# Sheet1.net
KiCad netlist of a schematic drawn in Altium Designer
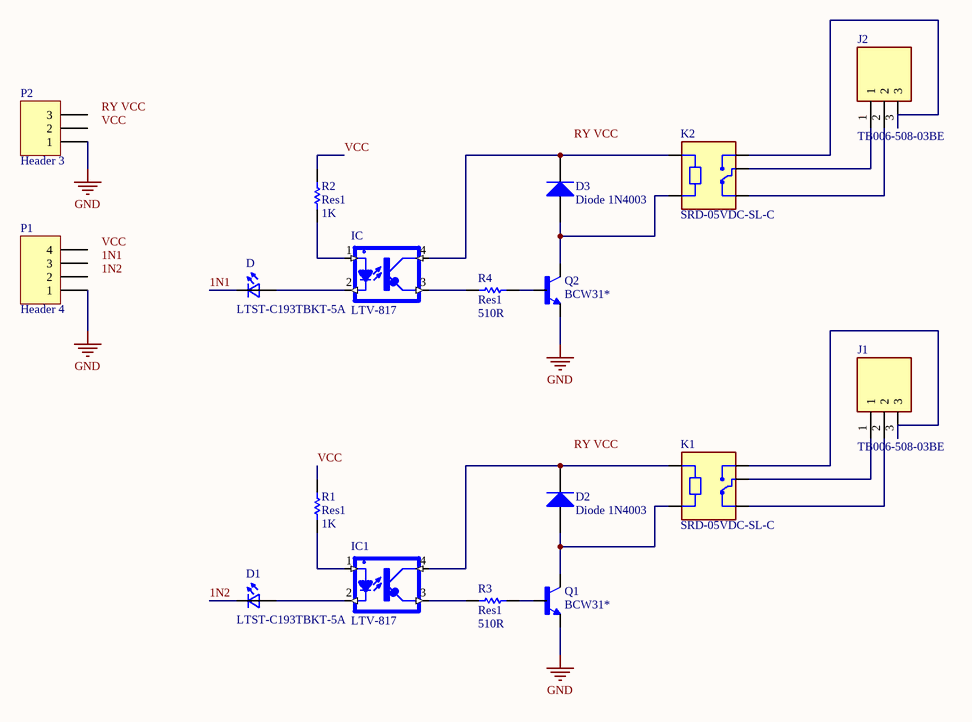
[diagram p0: Sheet1.SchDoc]

(export (version "E")
  (design (tool "Eeschema 10.0.6"))
  (components
    (comp (ref "D")
      (value "LTST-C193TBKT-5A")
      (footprint "0603")
      (description "Blue 470nm LED Indication - Discrete 2.8V 0603 _1608 Metric_")
      (fields (field (name "DIGI-KEY_PART_NUMBER") "160-1827-1-ND") (field (name "MF") "Lite-On Inc."))
      (libsource (lib "SnapEDAsch") (part "LTST-C193TBKT-5A"))
    )
    (comp (ref "D1")
      (value "LTST-C193TBKT-5A")
      (footprint "0603")
      (description "Blue 470nm LED Indication - Discrete 2.8V 0603 _1608 Metric_")
      (fields (field (name "DIGI-KEY_PART_NUMBER") "160-1827-1-ND") (field (name "MF") "Lite-On Inc."))
      (libsource (lib "SnapEDAsch") (part "LTST-C193TBKT-5A"))
    )
    (comp (ref "D2")
      (value "Diode 1N4003")
      (footprint "DO-41")
      (description "1 Amp General Purpose Rectifier")
      (fields (field (name "PUBLISHER") "Altium Limited"))
      (libsource (lib "Miscellaneous Devices") (part "Diode 1N4003"))
    )
    (comp (ref "D3")
      (value "Diode 1N4003")
      (footprint "DO-41")
      (description "1 Amp General Purpose Rectifier")
      (fields (field (name "PUBLISHER") "Altium Limited"))
      (libsource (lib "Miscellaneous Devices") (part "Diode 1N4003"))
    )
    (comp (ref "IC")
      (value "LTV-817")
      (footprint "DIP-4")
      (description "Optoisolator Transistor Output 5000Vrms 1 Channel 4-SMD")
      (fields (field (name "MF") "Lite-On Electronics"))
      (libsource (lib "SnapEDAsch") (part "LTV-817"))
    )
    (comp (ref "IC1")
      (value "LTV-817")
      (footprint "DIP-4")
      (description "Optoisolator Transistor Output 5000Vrms 1 Channel 4-SMD")
      (fields (field (name "MF") "Lite-On Electronics"))
      (libsource (lib "SnapEDAsch") (part "LTV-817"))
    )
    (comp (ref "J1")
      (value "TB006-508-03BE")
      (footprint "CUI_TB006-508-03BE")
      (description "2~24 Poles, Screw Type, Horizontal, 5.08 Pitch, 26~14 (AWG), Terminal Block Connector")
      (fields (field (name "MF") "CUI Devices"))
      (libsource (lib "TB006-508-03BE") (part "TB006-508-03BE"))
    )
    (comp (ref "J2")
      (value "TB006-508-03BE")
      (footprint "CUI_TB006-508-03BE")
      (description "2~24 Poles, Screw Type, Horizontal, 5.08 Pitch, 26~14 (AWG), Terminal Block Connector")
      (fields (field (name "MF") "CUI Devices"))
      (libsource (lib "TB006-508-03BE") (part "TB006-508-03BE"))
    )
    (comp (ref "K1")
      (value "SRD-05VDC-SL-C")
      (footprint "RELAY_SRD-05VDC-SL-C")
      (fields (field (name "MF") "Songle Relay"))
      (libsource (lib "SRD-05VDC-SL-C") (part "SRD-05VDC-SL-C"))
    )
    (comp (ref "K2")
      (value "SRD-05VDC-SL-C")
      (footprint "RELAY_SRD-05VDC-SL-C")
      (fields (field (name "MF") "Songle Relay"))
      (libsource (lib "SRD-05VDC-SL-C") (part "SRD-05VDC-SL-C"))
    )
    (comp (ref "P1")
      (value "Header 4")
      (footprint "HDR1X4")
      (description "Header, 4-Pin")
      (fields (field (name "PUBLISHER") "Altium Limited"))
      (libsource (lib "Miscellaneous Connectors") (part "Header 4"))
    )
    (comp (ref "P2")
      (value "Header 3")
      (footprint "HDR1X3")
      (description "Header, 3-Pin")
      (fields (field (name "PUBLISHER") "Altium Limited"))
      (libsource (lib "Miscellaneous Connectors") (part "Header 3"))
    )
    (comp (ref "Q1")
      (value "BCW31*")
      (footprint "SOT23-BEC")
      (description "Bipolar (BJT) Transistor NPN General Purpose Amplifier Surface Mount")
      (fields (field (name "MF") "ON Semiconductor") (field (name "MP") "BCW31"))
      (libsource (lib "BCW31") (part "BCW31*"))
    )
    (comp (ref "Q2")
      (value "BCW31*")
      (footprint "SOT23-BEC")
      (description "Bipolar (BJT) Transistor NPN General Purpose Amplifier Surface Mount")
      (fields (field (name "MF") "ON Semiconductor") (field (name "MP") "BCW31"))
      (libsource (lib "BCW31") (part "BCW31*"))
    )
    (comp (ref "R1")
      (value "Res1")
      (footprint "AXIAL-0.3")
      (description "Resistor")
      (fields (field (name "ALTIUM_VALUE") "1K") (field (name "PUBLISHER") "Altium Limited"))
      (libsource (lib "Miscellaneous Devices") (part "Res1"))
    )
    (comp (ref "R2")
      (value "Res1")
      (footprint "AXIAL-0.3")
      (description "Resistor")
      (fields (field (name "ALTIUM_VALUE") "1K") (field (name "PUBLISHER") "Altium Limited"))
      (libsource (lib "Miscellaneous Devices") (part "Res1"))
    )
    (comp (ref "R3")
      (value "Res1")
      (footprint "AXIAL-0.3")
      (description "Resistor")
      (fields (field (name "ALTIUM_VALUE") "510R") (field (name "PUBLISHER") "Altium Limited"))
      (libsource (lib "Miscellaneous Devices") (part "Res1"))
    )
    (comp (ref "R4")
      (value "Res1")
      (footprint "AXIAL-0.3")
      (description "Resistor")
      (fields (field (name "ALTIUM_VALUE") "510R") (field (name "PUBLISHER") "Altium Limited"))
      (libsource (lib "Miscellaneous Devices") (part "Res1"))
    )
  )
  (nets
    (net (code "1") (name "/1N1") (class "Default")
      (node (ref "D") (pin "1") (pinfunction "K2_1") (pintype "passive"))
    )
    (net (code "2") (name "/1N2") (class "Default")
      (node (ref "D1") (pin "1") (pinfunction "K2_1") (pintype "passive"))
    )
    (net (code "4") (name "/VCC") (class "Default")
      (node (ref "R1") (pin "2") (pinfunction "2_2") (pintype "passive"))
      (node (ref "R2") (pin "2") (pinfunction "2_2") (pintype "passive"))
    )
    (net (code "5") (name "GND") (class "Default")
      (node (ref "P1") (pin "1") (pinfunction "1_1") (pintype "passive"))
      (node (ref "P2") (pin "1") (pinfunction "1_1") (pintype "passive"))
      (node (ref "Q1") (pin "E") (pinfunction "E_E") (pintype "passive"))
      (node (ref "Q2") (pin "E") (pinfunction "E_E") (pintype "passive"))
    )
    (net (code "6") (name "Net-(D-A2)") (class "Default")
      (node (ref "D") (pin "2") (pinfunction "A2_2") (pintype "passive"))
      (node (ref "IC") (pin "2") (pinfunction "2_2") (pintype "output"))
    )
    (net (code "7") (name "Net-(D1-A2)") (class "Default")
      (node (ref "D1") (pin "2") (pinfunction "A2_2") (pintype "passive"))
      (node (ref "IC1") (pin "2") (pinfunction "2_2") (pintype "output"))
    )
    (net (code "8") (name "Net-(D2-A)") (class "Default")
      (node (ref "D2") (pin "1") (pinfunction "A_1") (pintype "passive"))
      (node (ref "K1") (pin "A2") (pinfunction "A2_A2") (pintype "passive"))
      (node (ref "Q1") (pin "C") (pinfunction "C_C") (pintype "passive"))
    )
    (net (code "9") (name "Net-(D2-K)") (class "Default")
      (node (ref "D2") (pin "2") (pinfunction "K_2") (pintype "passive"))
      (node (ref "IC1") (pin "4") (pinfunction "4_4") (pintype "input"))
      (node (ref "K1") (pin "A1") (pinfunction "A1_A1") (pintype "passive"))
    )
    (net (code "10") (name "Net-(D3-A)") (class "Default")
      (node (ref "D3") (pin "1") (pinfunction "A_1") (pintype "passive"))
      (node (ref "K2") (pin "A2") (pinfunction "A2_A2") (pintype "passive"))
      (node (ref "Q2") (pin "C") (pinfunction "C_C") (pintype "passive"))
    )
    (net (code "11") (name "Net-(D3-K)") (class "Default")
      (node (ref "D3") (pin "2") (pinfunction "K_2") (pintype "passive"))
      (node (ref "IC") (pin "4") (pinfunction "4_4") (pintype "input"))
      (node (ref "K2") (pin "A1") (pinfunction "A1_A1") (pintype "passive"))
    )
    (net (code "12") (name "Net-(IC-Pad1)") (class "Default")
      (node (ref "IC") (pin "1") (pinfunction "1_1") (pintype "input"))
      (node (ref "R2") (pin "1") (pinfunction "1_1") (pintype "passive"))
    )
    (net (code "13") (name "Net-(IC-Pad3)") (class "Default")
      (node (ref "IC") (pin "3") (pinfunction "3_3") (pintype "output"))
      (node (ref "R4") (pin "1") (pinfunction "1_1") (pintype "passive"))
    )
    (net (code "14") (name "Net-(IC1-Pad1)") (class "Default")
      (node (ref "IC1") (pin "1") (pinfunction "1_1") (pintype "input"))
      (node (ref "R1") (pin "1") (pinfunction "1_1") (pintype "passive"))
    )
    (net (code "15") (name "Net-(IC1-Pad3)") (class "Default")
      (node (ref "IC1") (pin "3") (pinfunction "3_3") (pintype "output"))
      (node (ref "R3") (pin "1") (pinfunction "1_1") (pintype "passive"))
    )
    (net (code "16") (name "Net-(J1-Pad1)") (class "Default")
      (node (ref "J1") (pin "1") (pinfunction "1_1") (pintype "passive"))
      (node (ref "K1") (pin "COM") (pinfunction "COM_COM") (pintype "passive"))
    )
    (net (code "17") (name "Net-(J1-Pad2)") (class "Default")
      (node (ref "J1") (pin "2") (pinfunction "2_2") (pintype "passive"))
      (node (ref "K1") (pin "NC") (pinfunction "NC_NC") (pintype "passive"))
    )
    (net (code "18") (name "Net-(J1-Pad3)") (class "Default")
      (node (ref "J1") (pin "3") (pinfunction "3_3") (pintype "passive"))
      (node (ref "K1") (pin "NO") (pinfunction "NO_NO") (pintype "passive"))
    )
    (net (code "19") (name "Net-(J2-Pad1)") (class "Default")
      (node (ref "J2") (pin "1") (pinfunction "1_1") (pintype "passive"))
      (node (ref "K2") (pin "COM") (pinfunction "COM_COM") (pintype "passive"))
    )
    (net (code "20") (name "Net-(J2-Pad2)") (class "Default")
      (node (ref "J2") (pin "2") (pinfunction "2_2") (pintype "passive"))
      (node (ref "K2") (pin "NC") (pinfunction "NC_NC") (pintype "passive"))
    )
    (net (code "21") (name "Net-(J2-Pad3)") (class "Default")
      (node (ref "J2") (pin "3") (pinfunction "3_3") (pintype "passive"))
      (node (ref "K2") (pin "NO") (pinfunction "NO_NO") (pintype "passive"))
    )
    (net (code "22") (name "Net-(Q1-PadB)") (class "Default")
      (node (ref "Q1") (pin "B") (pinfunction "B_B") (pintype "passive"))
      (node (ref "R3") (pin "2") (pinfunction "2_2") (pintype "passive"))
    )
    (net (code "23") (name "Net-(Q2-PadB)") (class "Default")
      (node (ref "Q2") (pin "B") (pinfunction "B_B") (pintype "passive"))
      (node (ref "R4") (pin "2") (pinfunction "2_2") (pintype "passive"))
    )
    (net (code "24") (name "unconnected-(P1-Pad2)") (class "Default")
      (node (ref "P1") (pin "2") (pinfunction "2_2") (pintype "passive"))
    )
    (net (code "25") (name "unconnected-(P1-Pad3)") (class "Default")
      (node (ref "P1") (pin "3") (pinfunction "3_3") (pintype "passive"))
    )
    (net (code "26") (name "unconnected-(P1-Pad4)") (class "Default")
      (node (ref "P1") (pin "4") (pinfunction "4_4") (pintype "passive"))
    )
    (net (code "27") (name "unconnected-(P2-Pad2)") (class "Default")
      (node (ref "P2") (pin "2") (pinfunction "2_2") (pintype "passive"))
    )
    (net (code "28") (name "unconnected-(P2-Pad3)") (class "Default")
      (node (ref "P2") (pin "3") (pinfunction "3_3") (pintype "passive"))
    )
  )
)
